# slider_cap_v0_1.net
KiCad netlist of a schematic drawn in EAGLE
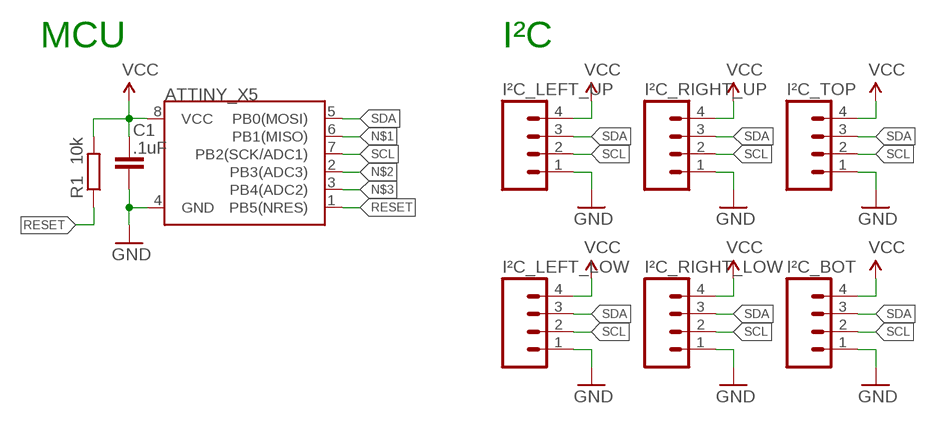
[diagram p0: schematic, sheet 1]

(export (version "E")
  (design (tool "Eeschema 10.0.6"))
  (components
    (comp (ref "ATTINY_X5")
      (value "ATTINY45TINY45-20-SMT")
      (footprint "eagle-import:SO08-EIAJ")
      (libsource (lib "eagle-import") (part "ATTINY45TINY45-20-SMT"))
    )
    (comp (ref "C1")
      (value ".1uF")
      (footprint "eagle-import:C805")
      (libsource (lib "eagle-import") (part "CAPACITOR_NPOL-0805"))
    )
    (comp (ref "I²C_BOT")
      (value "M04PTH")
      (footprint "eagle-import:1X04")
      (libsource (lib "eagle-import") (part "M04PTH"))
    )
    (comp (ref "I²C_LEFT_LOW")
      (value "M04PTH")
      (footprint "eagle-import:1X04")
      (libsource (lib "eagle-import") (part "M04PTH"))
    )
    (comp (ref "I²C_LEFT_UP")
      (value "M04PTH")
      (footprint "eagle-import:1X04")
      (libsource (lib "eagle-import") (part "M04PTH"))
    )
    (comp (ref "I²C_RIGHT_LOW")
      (value "M04PTH")
      (footprint "eagle-import:1X04")
      (libsource (lib "eagle-import") (part "M04PTH"))
    )
    (comp (ref "I²C_RIGHT_UP")
      (value "M04PTH")
      (footprint "eagle-import:1X04")
      (libsource (lib "eagle-import") (part "M04PTH"))
    )
    (comp (ref "I²C_TOP")
      (value "M04PTH")
      (footprint "eagle-import:1X04")
      (libsource (lib "eagle-import") (part "M04PTH"))
    )
    (comp (ref "R1")
      (value "10k")
      (footprint "eagle-import:R805")
      (libsource (lib "eagle-import") (part "RESISTOR-0805R805"))
    )
  )
  (nets
    (net (code "1") (name "GND") (class "Default")
      (node (ref "ATTINY_X5") (pin "4") (pinfunction "GND_4") (pintype "bidirectional"))
      (node (ref "C1") (pin "2") (pinfunction "2_2") (pintype "passive"))
      (node (ref "I²C_BOT") (pin "1") (pinfunction "1_1") (pintype "passive"))
      (node (ref "I²C_LEFT_LOW") (pin "1") (pinfunction "1_1") (pintype "passive"))
      (node (ref "I²C_LEFT_UP") (pin "1") (pinfunction "1_1") (pintype "passive"))
      (node (ref "I²C_RIGHT_LOW") (pin "1") (pinfunction "1_1") (pintype "passive"))
      (node (ref "I²C_RIGHT_UP") (pin "1") (pinfunction "1_1") (pintype "passive"))
      (node (ref "I²C_TOP") (pin "1") (pinfunction "1_1") (pintype "passive"))
    )
    (net (code "2") (name "N$1") (class "Default")
      (node (ref "ATTINY_X5") (pin "6") (pinfunction "PB1(MISO)_6") (pintype "bidirectional"))
    )
    (net (code "3") (name "N$2") (class "Default")
      (node (ref "ATTINY_X5") (pin "2") (pinfunction "PB3(ADC3)_2") (pintype "bidirectional"))
    )
    (net (code "4") (name "N$3") (class "Default")
      (node (ref "ATTINY_X5") (pin "3") (pinfunction "PB4(ADC2)_3") (pintype "bidirectional"))
    )
    (net (code "5") (name "RESET") (class "Default")
      (node (ref "ATTINY_X5") (pin "1") (pinfunction "PB5(NRES)_1") (pintype "bidirectional"))
      (node (ref "R1") (pin "1") (pinfunction "1_1") (pintype "passive"))
    )
    (net (code "6") (name "SCL") (class "Default")
      (node (ref "ATTINY_X5") (pin "7") (pinfunction "PB2(SCK/ADC1)_7") (pintype "bidirectional"))
      (node (ref "I²C_BOT") (pin "2") (pinfunction "2_2") (pintype "passive"))
      (node (ref "I²C_LEFT_LOW") (pin "2") (pinfunction "2_2") (pintype "passive"))
      (node (ref "I²C_LEFT_UP") (pin "2") (pinfunction "2_2") (pintype "passive"))
      (node (ref "I²C_RIGHT_LOW") (pin "2") (pinfunction "2_2") (pintype "passive"))
      (node (ref "I²C_RIGHT_UP") (pin "2") (pinfunction "2_2") (pintype "passive"))
      (node (ref "I²C_TOP") (pin "2") (pinfunction "2_2") (pintype "passive"))
    )
    (net (code "7") (name "SDA") (class "Default")
      (node (ref "ATTINY_X5") (pin "5") (pinfunction "PB0(MOSI)_5") (pintype "bidirectional"))
      (node (ref "I²C_BOT") (pin "3") (pinfunction "3_3") (pintype "passive"))
      (node (ref "I²C_LEFT_LOW") (pin "3") (pinfunction "3_3") (pintype "passive"))
      (node (ref "I²C_LEFT_UP") (pin "3") (pinfunction "3_3") (pintype "passive"))
      (node (ref "I²C_RIGHT_LOW") (pin "3") (pinfunction "3_3") (pintype "passive"))
      (node (ref "I²C_RIGHT_UP") (pin "3") (pinfunction "3_3") (pintype "passive"))
      (node (ref "I²C_TOP") (pin "3") (pinfunction "3_3") (pintype "passive"))
    )
    (net (code "8") (name "VCC") (class "Default")
      (node (ref "ATTINY_X5") (pin "8") (pinfunction "VCC_8") (pintype "bidirectional"))
      (node (ref "C1") (pin "1") (pinfunction "1_1") (pintype "passive"))
      (node (ref "I²C_BOT") (pin "4") (pinfunction "4_4") (pintype "passive"))
      (node (ref "I²C_LEFT_LOW") (pin "4") (pinfunction "4_4") (pintype "passive"))
      (node (ref "I²C_LEFT_UP") (pin "4") (pinfunction "4_4") (pintype "passive"))
      (node (ref "I²C_RIGHT_LOW") (pin "4") (pinfunction "4_4") (pintype "passive"))
      (node (ref "I²C_RIGHT_UP") (pin "4") (pinfunction "4_4") (pintype "passive"))
      (node (ref "I²C_TOP") (pin "4") (pinfunction "4_4") (pintype "passive"))
      (node (ref "R1") (pin "2") (pinfunction "2_2") (pintype "passive"))
    )
  )
)
